# memory.net
KiCad netlist of a schematic drawn in EAGLE
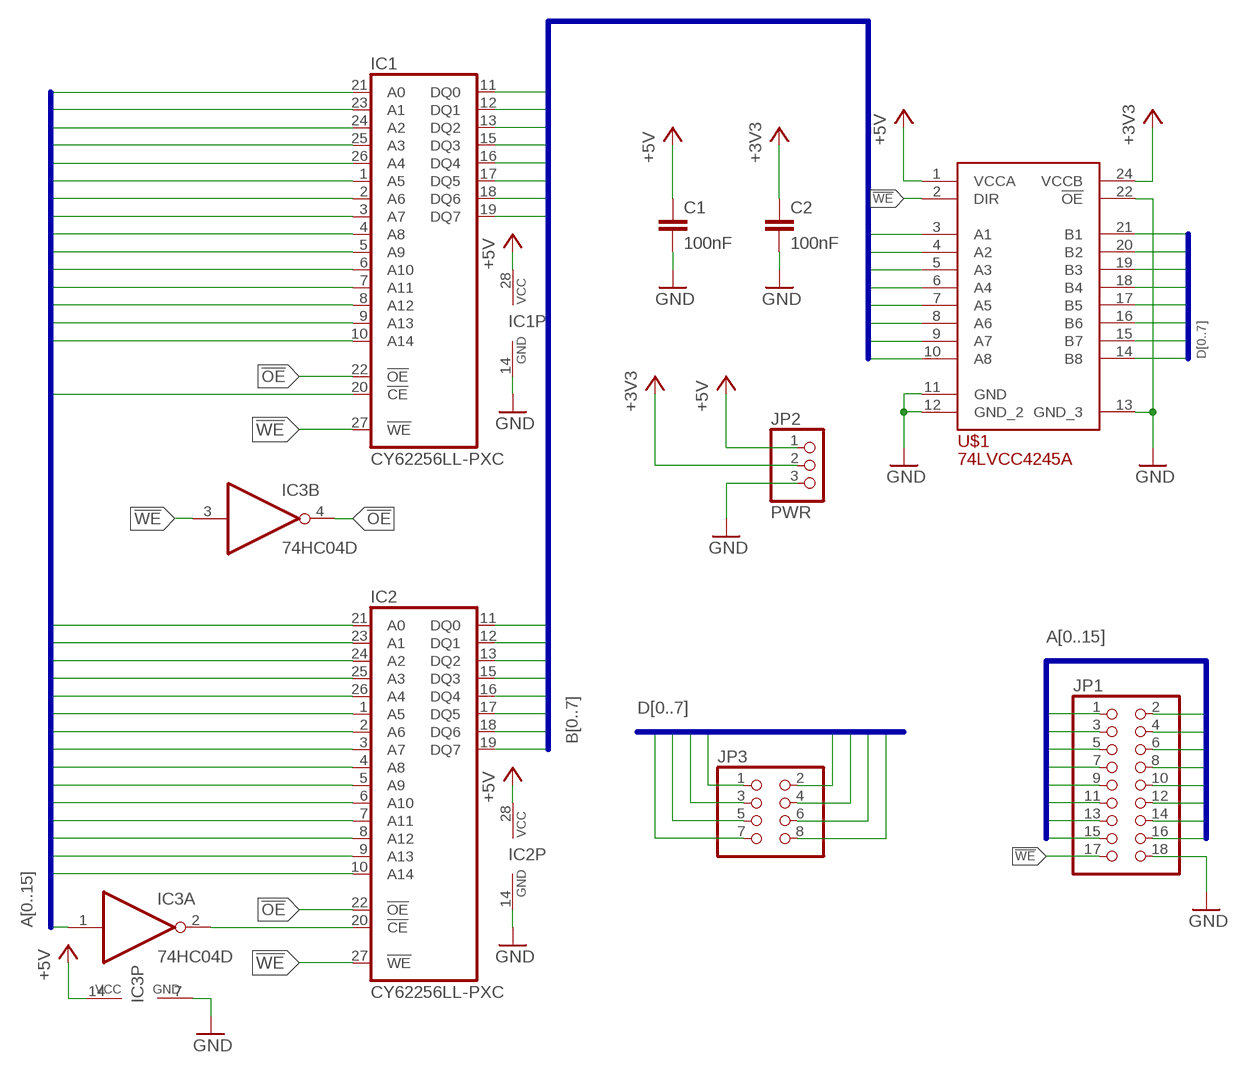
[diagram p0: schematic, sheet 1]

(export (version "E")
  (design (tool "Eeschema 10.0.6"))
  (components
    (comp (ref "C1")
      (value "100nF")
      (footprint "eagle-import:C0805")
      (libsource (lib "eagle-import") (part "C-EUC0805"))
    )
    (comp (ref "C2")
      (value "100nF")
      (footprint "eagle-import:C0805")
      (libsource (lib "eagle-import") (part "C-EUC0805"))
    )
    (comp (ref "IC1")
      (value "CY62256LL-PXC")
      (footprint "eagle-import:DIL28-6")
      (libsource (lib "eagle-import") (part "CY62256LL-?PXC"))
    )
    (comp (ref "IC2")
      (value "CY62256LL-PXC")
      (footprint "eagle-import:DIL28-6")
      (libsource (lib "eagle-import") (part "CY62256LL-?PXC"))
    )
    (comp (ref "IC3")
      (value "74HC04D")
      (footprint "eagle-import:SO14")
      (libsource (lib "eagle-import") (part "7404DHC"))
    )
    (comp (ref "JP1")
      (value "PINHD-2X9")
      (footprint "eagle-import:2X09")
      (libsource (lib "eagle-import") (part "PINHD-2X9"))
    )
    (comp (ref "JP2")
      (value "PWR")
      (footprint "eagle-import:1X03")
      (libsource (lib "eagle-import") (part "PINHD-1X3"))
    )
    (comp (ref "JP3")
      (value "PINHD-2X4")
      (footprint "eagle-import:2X04")
      (libsource (lib "eagle-import") (part "PINHD-2X4"))
    )
    (comp (ref "U$1")
      (value "74LCC4245A")
      (footprint "eagle-import:SO24W")
      (libsource (lib "eagle-import") (part "74LCC4245A"))
    )
  )
  (nets
    (net (code "1") (name "+3V3") (class "Default")
      (node (ref "C2") (pin "1") (pinfunction "1_1") (pintype "passive"))
      (node (ref "JP2") (pin "2") (pinfunction "2_2") (pintype "passive"))
      (node (ref "U$1") (pin "24") (pinfunction "VCCB_24") (pintype "bidirectional"))
    )
    (net (code "2") (name "+5V") (class "Default")
      (node (ref "C1") (pin "1") (pinfunction "1_1") (pintype "passive"))
      (node (ref "IC1") (pin "28") (pinfunction "VCC_28") (pintype "power_in"))
      (node (ref "IC2") (pin "28") (pinfunction "VCC_28") (pintype "power_in"))
      (node (ref "IC3") (pin "14") (pinfunction "VCC_14") (pintype "power_in"))
      (node (ref "JP2") (pin "1") (pinfunction "1_1") (pintype "passive"))
      (node (ref "U$1") (pin "1") (pinfunction "VCCA_1") (pintype "bidirectional"))
    )
    (net (code "3") (name "/A0") (class "Default")
      (node (ref "IC1") (pin "21") (pinfunction "A0_21") (pintype "input"))
      (node (ref "IC2") (pin "21") (pinfunction "A0_21") (pintype "input"))
      (node (ref "JP1") (pin "1") (pinfunction "1_1") (pintype "passive"))
    )
    (net (code "4") (name "/A1") (class "Default")
      (node (ref "IC1") (pin "23") (pinfunction "A1_23") (pintype "input"))
      (node (ref "IC2") (pin "23") (pinfunction "A1_23") (pintype "input"))
      (node (ref "JP1") (pin "2") (pinfunction "2_2") (pintype "passive"))
    )
    (net (code "5") (name "/A2") (class "Default")
      (node (ref "IC1") (pin "24") (pinfunction "A2_24") (pintype "input"))
      (node (ref "IC2") (pin "24") (pinfunction "A2_24") (pintype "input"))
      (node (ref "JP1") (pin "3") (pinfunction "3_3") (pintype "passive"))
    )
    (net (code "6") (name "/A3") (class "Default")
      (node (ref "IC1") (pin "25") (pinfunction "A3_25") (pintype "input"))
      (node (ref "IC2") (pin "25") (pinfunction "A3_25") (pintype "input"))
      (node (ref "JP1") (pin "4") (pinfunction "4_4") (pintype "passive"))
    )
    (net (code "7") (name "/A4") (class "Default")
      (node (ref "IC1") (pin "26") (pinfunction "A4_26") (pintype "input"))
      (node (ref "IC2") (pin "26") (pinfunction "A4_26") (pintype "input"))
      (node (ref "JP1") (pin "5") (pinfunction "5_5") (pintype "passive"))
    )
    (net (code "8") (name "/A5") (class "Default")
      (node (ref "IC1") (pin "1") (pinfunction "A5_1") (pintype "input"))
      (node (ref "IC2") (pin "1") (pinfunction "A5_1") (pintype "input"))
      (node (ref "JP1") (pin "6") (pinfunction "6_6") (pintype "passive"))
    )
    (net (code "9") (name "/A6") (class "Default")
      (node (ref "IC1") (pin "2") (pinfunction "A6_2") (pintype "input"))
      (node (ref "IC2") (pin "2") (pinfunction "A6_2") (pintype "input"))
      (node (ref "JP1") (pin "7") (pinfunction "7_7") (pintype "passive"))
    )
    (net (code "10") (name "/A7") (class "Default")
      (node (ref "IC1") (pin "3") (pinfunction "A7_3") (pintype "input"))
      (node (ref "IC2") (pin "3") (pinfunction "A7_3") (pintype "input"))
      (node (ref "JP1") (pin "8") (pinfunction "8_8") (pintype "passive"))
    )
    (net (code "11") (name "/A8") (class "Default")
      (node (ref "IC1") (pin "4") (pinfunction "A8_4") (pintype "input"))
      (node (ref "IC2") (pin "4") (pinfunction "A8_4") (pintype "input"))
      (node (ref "JP1") (pin "9") (pinfunction "9_9") (pintype "passive"))
    )
    (net (code "12") (name "/A9") (class "Default")
      (node (ref "IC1") (pin "5") (pinfunction "A9_5") (pintype "input"))
      (node (ref "IC2") (pin "5") (pinfunction "A9_5") (pintype "input"))
      (node (ref "JP1") (pin "10") (pinfunction "10_10") (pintype "passive"))
    )
    (net (code "13") (name "/A10") (class "Default")
      (node (ref "IC1") (pin "6") (pinfunction "A10_6") (pintype "input"))
      (node (ref "IC2") (pin "6") (pinfunction "A10_6") (pintype "input"))
      (node (ref "JP1") (pin "11") (pinfunction "11_11") (pintype "passive"))
    )
    (net (code "14") (name "/A11") (class "Default")
      (node (ref "IC1") (pin "7") (pinfunction "A11_7") (pintype "input"))
      (node (ref "IC2") (pin "7") (pinfunction "A11_7") (pintype "input"))
      (node (ref "JP1") (pin "12") (pinfunction "12_12") (pintype "passive"))
    )
    (net (code "15") (name "/A12") (class "Default")
      (node (ref "IC1") (pin "8") (pinfunction "A12_8") (pintype "input"))
      (node (ref "IC2") (pin "8") (pinfunction "A12_8") (pintype "input"))
      (node (ref "JP1") (pin "13") (pinfunction "13_13") (pintype "passive"))
    )
    (net (code "16") (name "/A13") (class "Default")
      (node (ref "IC1") (pin "9") (pinfunction "A13_9") (pintype "input"))
      (node (ref "IC2") (pin "9") (pinfunction "A13_9") (pintype "input"))
      (node (ref "JP1") (pin "14") (pinfunction "14_14") (pintype "passive"))
    )
    (net (code "17") (name "/A14") (class "Default")
      (node (ref "IC1") (pin "10") (pinfunction "A14_10") (pintype "input"))
      (node (ref "IC2") (pin "10") (pinfunction "A14_10") (pintype "input"))
      (node (ref "JP1") (pin "15") (pinfunction "15_15") (pintype "passive"))
    )
    (net (code "18") (name "/A15") (class "Default")
      (node (ref "IC1") (pin "20") (pinfunction "~{CE}_20") (pintype "input"))
      (node (ref "IC3") (pin "1") (pinfunction "I_1") (pintype "input"))
      (node (ref "JP1") (pin "16") (pinfunction "16_16") (pintype "passive"))
    )
    (net (code "20") (name "/B0") (class "Default")
      (node (ref "IC1") (pin "11") (pinfunction "DQ0_11") (pintype "bidirectional"))
      (node (ref "IC2") (pin "11") (pinfunction "DQ0_11") (pintype "bidirectional"))
      (node (ref "U$1") (pin "3") (pinfunction "A1_3") (pintype "bidirectional"))
    )
    (net (code "21") (name "/B1") (class "Default")
      (node (ref "IC1") (pin "12") (pinfunction "DQ1_12") (pintype "bidirectional"))
      (node (ref "IC2") (pin "12") (pinfunction "DQ1_12") (pintype "bidirectional"))
      (node (ref "U$1") (pin "4") (pinfunction "A2_4") (pintype "bidirectional"))
    )
    (net (code "22") (name "/B2") (class "Default")
      (node (ref "IC1") (pin "13") (pinfunction "DQ2_13") (pintype "bidirectional"))
      (node (ref "IC2") (pin "13") (pinfunction "DQ2_13") (pintype "bidirectional"))
      (node (ref "U$1") (pin "5") (pinfunction "A3_5") (pintype "bidirectional"))
    )
    (net (code "23") (name "/B3") (class "Default")
      (node (ref "IC1") (pin "15") (pinfunction "DQ3_15") (pintype "bidirectional"))
      (node (ref "IC2") (pin "15") (pinfunction "DQ3_15") (pintype "bidirectional"))
      (node (ref "U$1") (pin "6") (pinfunction "A4_6") (pintype "bidirectional"))
    )
    (net (code "24") (name "/B4") (class "Default")
      (node (ref "IC1") (pin "16") (pinfunction "DQ4_16") (pintype "bidirectional"))
      (node (ref "IC2") (pin "16") (pinfunction "DQ4_16") (pintype "bidirectional"))
      (node (ref "U$1") (pin "7") (pinfunction "A5_7") (pintype "bidirectional"))
    )
    (net (code "25") (name "/B5") (class "Default")
      (node (ref "IC1") (pin "17") (pinfunction "DQ5_17") (pintype "bidirectional"))
      (node (ref "IC2") (pin "17") (pinfunction "DQ5_17") (pintype "bidirectional"))
      (node (ref "U$1") (pin "8") (pinfunction "A6_8") (pintype "bidirectional"))
    )
    (net (code "26") (name "/B6") (class "Default")
      (node (ref "IC1") (pin "18") (pinfunction "DQ6_18") (pintype "bidirectional"))
      (node (ref "IC2") (pin "18") (pinfunction "DQ6_18") (pintype "bidirectional"))
      (node (ref "U$1") (pin "9") (pinfunction "A7_9") (pintype "bidirectional"))
    )
    (net (code "27") (name "/B7") (class "Default")
      (node (ref "IC1") (pin "19") (pinfunction "DQ7_19") (pintype "bidirectional"))
      (node (ref "IC2") (pin "19") (pinfunction "DQ7_19") (pintype "bidirectional"))
      (node (ref "U$1") (pin "10") (pinfunction "A8_10") (pintype "bidirectional"))
    )
    (net (code "29") (name "/D0") (class "Default")
      (node (ref "JP3") (pin "1") (pinfunction "1_1") (pintype "passive"))
      (node (ref "U$1") (pin "21") (pinfunction "B1_21") (pintype "bidirectional"))
    )
    (net (code "30") (name "/D1") (class "Default")
      (node (ref "JP3") (pin "2") (pinfunction "2_2") (pintype "passive"))
      (node (ref "U$1") (pin "20") (pinfunction "B2_20") (pintype "bidirectional"))
    )
    (net (code "31") (name "/D2") (class "Default")
      (node (ref "JP3") (pin "3") (pinfunction "3_3") (pintype "passive"))
      (node (ref "U$1") (pin "19") (pinfunction "B3_19") (pintype "bidirectional"))
    )
    (net (code "32") (name "/D3") (class "Default")
      (node (ref "JP3") (pin "4") (pinfunction "4_4") (pintype "passive"))
      (node (ref "U$1") (pin "18") (pinfunction "B4_18") (pintype "bidirectional"))
    )
    (net (code "33") (name "/D4") (class "Default")
      (node (ref "JP3") (pin "5") (pinfunction "5_5") (pintype "passive"))
      (node (ref "U$1") (pin "17") (pinfunction "B5_17") (pintype "bidirectional"))
    )
    (net (code "34") (name "/D5") (class "Default")
      (node (ref "JP3") (pin "6") (pinfunction "6_6") (pintype "passive"))
      (node (ref "U$1") (pin "16") (pinfunction "B6_16") (pintype "bidirectional"))
    )
    (net (code "35") (name "/D6") (class "Default")
      (node (ref "JP3") (pin "7") (pinfunction "7_7") (pintype "passive"))
      (node (ref "U$1") (pin "15") (pinfunction "B7_15") (pintype "bidirectional"))
    )
    (net (code "36") (name "/D7") (class "Default")
      (node (ref "JP3") (pin "8") (pinfunction "8_8") (pintype "passive"))
      (node (ref "U$1") (pin "14") (pinfunction "B8_14") (pintype "bidirectional"))
    )
    (net (code "38") (name "/~{OE}") (class "Default")
      (node (ref "IC1") (pin "22") (pinfunction "~{OE}_22") (pintype "input"))
      (node (ref "IC2") (pin "22") (pinfunction "~{OE}_22") (pintype "input"))
      (node (ref "IC3") (pin "4") (pinfunction "O_4") (pintype "output"))
    )
    (net (code "39") (name "/~{WE}") (class "Default")
      (node (ref "IC1") (pin "27") (pinfunction "~{WE}_27") (pintype "input"))
      (node (ref "IC2") (pin "27") (pinfunction "~{WE}_27") (pintype "input"))
      (node (ref "IC3") (pin "3") (pinfunction "I_3") (pintype "input"))
      (node (ref "JP1") (pin "17") (pinfunction "17_17") (pintype "passive"))
      (node (ref "U$1") (pin "2") (pinfunction "DIR_2") (pintype "bidirectional"))
    )
    (net (code "40") (name "GND") (class "Default")
      (node (ref "C1") (pin "2") (pinfunction "2_2") (pintype "passive"))
      (node (ref "C2") (pin "2") (pinfunction "2_2") (pintype "passive"))
      (node (ref "IC1") (pin "14") (pinfunction "GND_14") (pintype "power_in"))
      (node (ref "IC2") (pin "14") (pinfunction "GND_14") (pintype "power_in"))
      (node (ref "IC3") (pin "7") (pinfunction "GND_7") (pintype "power_in"))
      (node (ref "JP1") (pin "18") (pinfunction "18_18") (pintype "passive"))
      (node (ref "JP2") (pin "3") (pinfunction "3_3") (pintype "passive"))
      (node (ref "U$1") (pin "11") (pinfunction "GND_11") (pintype "bidirectional"))
      (node (ref "U$1") (pin "12") (pinfunction "GND_2_12") (pintype "bidirectional"))
      (node (ref "U$1") (pin "13") (pinfunction "GND_3_13") (pintype "bidirectional"))
      (node (ref "U$1") (pin "22") (pinfunction "~{OE}_22") (pintype "bidirectional"))
    )
    (net (code "41") (name "Net-(IC2A-~{CE})") (class "Default")
      (node (ref "IC2") (pin "20") (pinfunction "~{CE}_20") (pintype "input"))
      (node (ref "IC3") (pin "2") (pinfunction "O_2") (pintype "output"))
    )
  )
)
